# V4-AddOnZigbee-DIL-V02-003.net
KiCad netlist of a schematic drawn in EAGLE
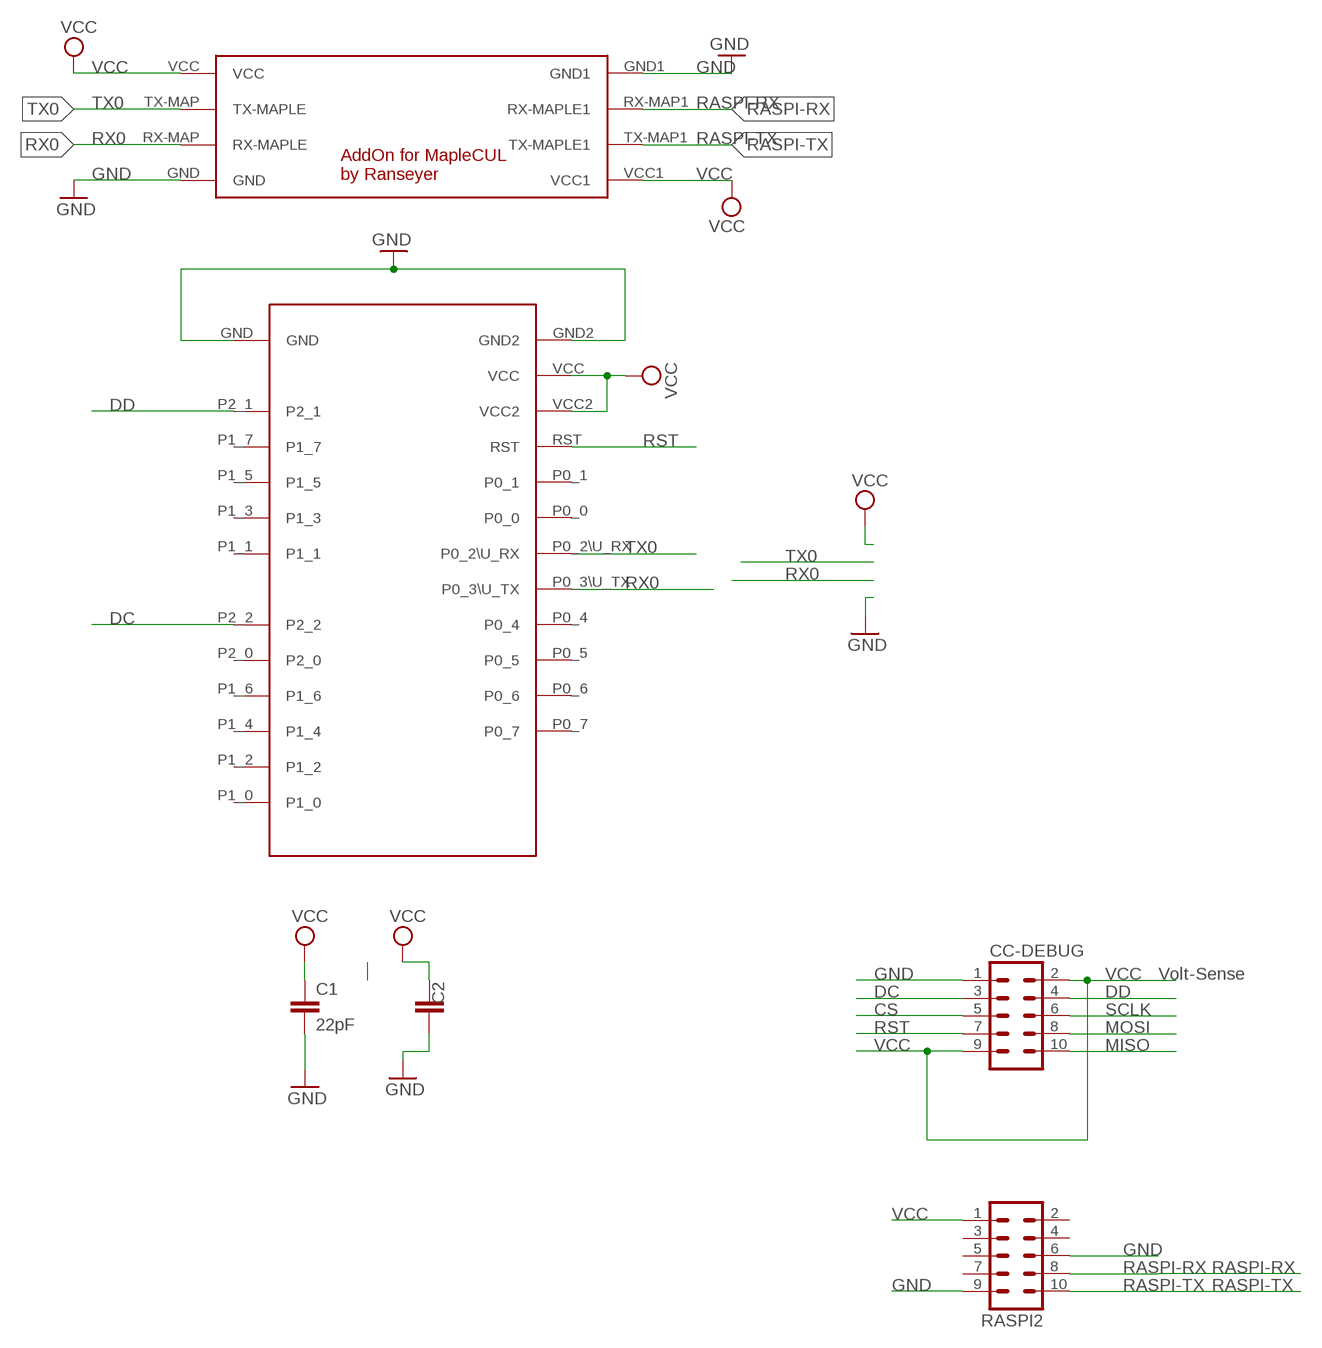
[diagram p0: schematic, sheet 1]

(export (version "E")
  (design (tool "Eeschema 10.0.6"))
  (components
    (comp (ref "C1")
      (value "22pF")
      (footprint "eagle-import:C0805")
      (libsource (lib "eagle-import") (part "C-EUC0805"))
    )
    (comp (ref "C2")
      (value "C-EUC1812")
      (footprint "eagle-import:C1812")
      (libsource (lib "eagle-import") (part "C-EUC1812"))
    )
    (comp (ref "CC-DEBUG")
      (value "CONN_05X2SHD_LOCK")
      (footprint "eagle-import:2X5-SHROUDED_LOCK")
      (libsource (lib "eagle-import") (part "CONN_05X2SHD_LOCK"))
    )
    (comp (ref "RASPI2")
      (value "MA05-2")
      (footprint "eagle-import:MA05-2")
      (libsource (lib "eagle-import") (part "MA05-2"))
    )
    (comp (ref "U$1")
      (value "MAPLE-CUL-ADDON-V01")
      (footprint "eagle-import:MAPLE-CUL-V01")
      (libsource (lib "eagle-import") (part "MAPLE-CUL-ADDON-V01"))
    )
    (comp (ref "U$3")
      (value "CC2530_MODULE")
      (footprint "eagle-import:CC2530_DIL")
      (libsource (lib "eagle-import") (part "CC2530_MODULE"))
    )
  )
  (nets
    (net (code "1") (name "/CS") (class "Default")
      (node (ref "CC-DEBUG") (pin "5") (pinfunction "5_5") (pintype "passive"))
    )
    (net (code "2") (name "/DC") (class "Default")
      (node (ref "CC-DEBUG") (pin "3") (pinfunction "3_3") (pintype "passive"))
      (node (ref "U$3") (pin "P2_2") (pinfunction "P2_2_P2_2") (pintype "bidirectional"))
    )
    (net (code "3") (name "/DD") (class "Default")
      (node (ref "CC-DEBUG") (pin "4") (pinfunction "4_4") (pintype "passive"))
      (node (ref "U$3") (pin "P2_1") (pinfunction "P2_1_P2_1") (pintype "bidirectional"))
    )
    (net (code "4") (name "/MISO") (class "Default")
      (node (ref "CC-DEBUG") (pin "10") (pinfunction "10_10") (pintype "passive"))
    )
    (net (code "5") (name "/MOSI") (class "Default")
      (node (ref "CC-DEBUG") (pin "8") (pinfunction "8_8") (pintype "passive"))
    )
    (net (code "6") (name "/RST") (class "Default")
      (node (ref "CC-DEBUG") (pin "7") (pinfunction "7_7") (pintype "passive"))
      (node (ref "U$3") (pin "RST") (pinfunction "RST_RST") (pintype "bidirectional"))
    )
    (net (code "7") (name "/SCLK") (class "Default")
      (node (ref "CC-DEBUG") (pin "6") (pinfunction "6_6") (pintype "passive"))
    )
    (net (code "8") (name "GND") (class "Default")
      (node (ref "C1") (pin "2") (pinfunction "2_2") (pintype "passive"))
      (node (ref "C2") (pin "1") (pinfunction "1_1") (pintype "passive"))
      (node (ref "CC-DEBUG") (pin "1") (pinfunction "1_1") (pintype "passive"))
      (node (ref "RASPI2") (pin "6") (pinfunction "6_6") (pintype "passive"))
      (node (ref "RASPI2") (pin "9") (pinfunction "9_9") (pintype "passive"))
      (node (ref "U$1") (pin "GND") (pinfunction "GND_GND") (pintype "bidirectional"))
      (node (ref "U$1") (pin "GND1") (pinfunction "GND1_GND1") (pintype "bidirectional"))
      (node (ref "U$3") (pin "GND") (pinfunction "GND_GND") (pintype "bidirectional"))
      (node (ref "U$3") (pin "GND2") (pinfunction "GND2_GND2") (pintype "bidirectional"))
    )
    (net (code "9") (name "RASPI-RX") (class "Default")
      (node (ref "RASPI2") (pin "8") (pinfunction "8_8") (pintype "passive"))
      (node (ref "U$1") (pin "RX-MAP1") (pinfunction "RX-MAPLE1_RX-MAP1") (pintype "bidirectional"))
    )
    (net (code "10") (name "RASPI-TX") (class "Default")
      (node (ref "RASPI2") (pin "10") (pinfunction "10_10") (pintype "passive"))
      (node (ref "U$1") (pin "TX-MAP1") (pinfunction "TX-MAPLE1_TX-MAP1") (pintype "bidirectional"))
    )
    (net (code "11") (name "RX0") (class "Default")
      (node (ref "U$1") (pin "RX-MAP") (pinfunction "RX-MAPLE_RX-MAP") (pintype "bidirectional"))
      (node (ref "U$3") (pin "P0_3\\U_TX") (pinfunction "P0_3\\U_TX_P0_3\\U_TX") (pintype "bidirectional"))
    )
    (net (code "12") (name "TX0") (class "Default")
      (node (ref "U$1") (pin "TX-MAP") (pinfunction "TX-MAPLE_TX-MAP") (pintype "bidirectional"))
      (node (ref "U$3") (pin "P0_2\\U_RX") (pinfunction "P0_2\\U_RX_P0_2\\U_RX") (pintype "bidirectional"))
    )
    (net (code "13") (name "VCC") (class "Default")
      (node (ref "C1") (pin "1") (pinfunction "1_1") (pintype "passive"))
      (node (ref "C2") (pin "2") (pinfunction "2_2") (pintype "passive"))
      (node (ref "CC-DEBUG") (pin "2") (pinfunction "2_2") (pintype "passive"))
      (node (ref "CC-DEBUG") (pin "9") (pinfunction "9_9") (pintype "passive"))
      (node (ref "RASPI2") (pin "1") (pinfunction "1_1") (pintype "passive"))
      (node (ref "U$1") (pin "VCC") (pinfunction "VCC_VCC") (pintype "bidirectional"))
      (node (ref "U$1") (pin "VCC1") (pinfunction "VCC1_VCC1") (pintype "bidirectional"))
      (node (ref "U$3") (pin "VCC") (pinfunction "VCC_VCC") (pintype "bidirectional"))
      (node (ref "U$3") (pin "VCC2") (pinfunction "VCC2_VCC2") (pintype "bidirectional"))
    )
    (net (code "14") (name "unconnected-(RASPI2-Pad2)") (class "Default")
      (node (ref "RASPI2") (pin "2") (pinfunction "2_2") (pintype "passive"))
    )
    (net (code "15") (name "unconnected-(RASPI2-Pad3)") (class "Default")
      (node (ref "RASPI2") (pin "3") (pinfunction "3_3") (pintype "passive"))
    )
    (net (code "16") (name "unconnected-(RASPI2-Pad4)") (class "Default")
      (node (ref "RASPI2") (pin "4") (pinfunction "4_4") (pintype "passive"))
    )
    (net (code "17") (name "unconnected-(RASPI2-Pad5)") (class "Default")
      (node (ref "RASPI2") (pin "5") (pinfunction "5_5") (pintype "passive"))
    )
    (net (code "18") (name "unconnected-(RASPI2-Pad7)") (class "Default")
      (node (ref "RASPI2") (pin "7") (pinfunction "7_7") (pintype "passive"))
    )
    (net (code "19") (name "unconnected-(U$3-PadP0_0)") (class "Default")
      (node (ref "U$3") (pin "P0_0") (pinfunction "P0_0_P0_0") (pintype "bidirectional"))
    )
    (net (code "20") (name "unconnected-(U$3-PadP0_1)") (class "Default")
      (node (ref "U$3") (pin "P0_1") (pinfunction "P0_1_P0_1") (pintype "bidirectional"))
    )
    (net (code "21") (name "unconnected-(U$3-PadP0_4)") (class "Default")
      (node (ref "U$3") (pin "P0_4") (pinfunction "P0_4_P0_4") (pintype "bidirectional"))
    )
    (net (code "22") (name "unconnected-(U$3-PadP0_5)") (class "Default")
      (node (ref "U$3") (pin "P0_5") (pinfunction "P0_5_P0_5") (pintype "bidirectional"))
    )
    (net (code "23") (name "unconnected-(U$3-PadP0_6)") (class "Default")
      (node (ref "U$3") (pin "P0_6") (pinfunction "P0_6_P0_6") (pintype "bidirectional"))
    )
    (net (code "24") (name "unconnected-(U$3-PadP0_7)") (class "Default")
      (node (ref "U$3") (pin "P0_7") (pinfunction "P0_7_P0_7") (pintype "bidirectional"))
    )
    (net (code "25") (name "unconnected-(U$3-PadP1_0)") (class "Default")
      (node (ref "U$3") (pin "P1_0") (pinfunction "P1_0_P1_0") (pintype "bidirectional"))
    )
    (net (code "26") (name "unconnected-(U$3-PadP1_1)") (class "Default")
      (node (ref "U$3") (pin "P1_1") (pinfunction "P1_1_P1_1") (pintype "bidirectional"))
    )
    (net (code "27") (name "unconnected-(U$3-PadP1_2)") (class "Default")
      (node (ref "U$3") (pin "P1_2") (pinfunction "P1_2_P1_2") (pintype "bidirectional"))
    )
    (net (code "28") (name "unconnected-(U$3-PadP1_3)") (class "Default")
      (node (ref "U$3") (pin "P1_3") (pinfunction "P1_3_P1_3") (pintype "bidirectional"))
    )
    (net (code "29") (name "unconnected-(U$3-PadP1_4)") (class "Default")
      (node (ref "U$3") (pin "P1_4") (pinfunction "P1_4_P1_4") (pintype "bidirectional"))
    )
    (net (code "30") (name "unconnected-(U$3-PadP1_5)") (class "Default")
      (node (ref "U$3") (pin "P1_5") (pinfunction "P1_5_P1_5") (pintype "bidirectional"))
    )
    (net (code "31") (name "unconnected-(U$3-PadP1_6)") (class "Default")
      (node (ref "U$3") (pin "P1_6") (pinfunction "P1_6_P1_6") (pintype "bidirectional"))
    )
    (net (code "32") (name "unconnected-(U$3-PadP1_7)") (class "Default")
      (node (ref "U$3") (pin "P1_7") (pinfunction "P1_7_P1_7") (pintype "bidirectional"))
    )
    (net (code "33") (name "unconnected-(U$3-PadP2_0)") (class "Default")
      (node (ref "U$3") (pin "P2_0") (pinfunction "P2_0_P2_0") (pintype "bidirectional"))
    )
  )
)
